# temperature.net
KiCad netlist of a schematic drawn in Altium Designer
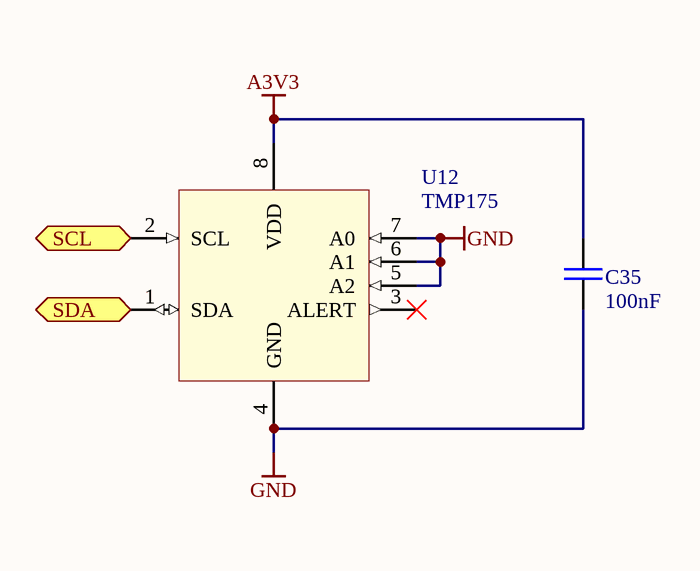
[diagram p0: temperature.SchDoc]

(export (version "E")
  (design (tool "Eeschema 10.0.6"))
  (components
    (comp (ref "C35")
      (value "100nF")
      (footprint "0603")
      (description "Capacitor")
      (fields (field (name "OWNER") "Nuno Brum"))
      (libsource (lib "Alcetronics_Devices") (part "CAP"))
    )
    (comp (ref "U12")
      (value "TMP175")
      (footprint "SOIC-8")
      (description "Digital Temperature Sensor")
      (libsource (lib "Alcetronics_IC") (part "TMP175"))
    )
  )
  (nets
    (net (code "1") (name "/SCL") (class "Default")
      (node (ref "U12") (pin "2") (pinfunction "SCL_2") (pintype "input"))
    )
    (net (code "2") (name "/SDA") (class "Default")
      (node (ref "U12") (pin "1") (pinfunction "SDA_1") (pintype "bidirectional"))
    )
    (net (code "3") (name "A3V3") (class "Default")
      (node (ref "C35") (pin "2") (pinfunction "2_2") (pintype "passive"))
      (node (ref "U12") (pin "8") (pinfunction "VDD_8") (pintype "power_in"))
    )
    (net (code "4") (name "GND") (class "Default")
      (node (ref "C35") (pin "1") (pinfunction "1_1") (pintype "passive"))
      (node (ref "U12") (pin "4") (pinfunction "GND_4") (pintype "power_in"))
      (node (ref "U12") (pin "5") (pinfunction "A2_5") (pintype "input"))
      (node (ref "U12") (pin "6") (pinfunction "A1_6") (pintype "input"))
      (node (ref "U12") (pin "7") (pinfunction "A0_7") (pintype "input"))
    )
    (net (code "5") (name "unconnected-(U12-ALERT-Pad3)") (class "Default")
      (node (ref "U12") (pin "3") (pinfunction "ALERT_3") (pintype "output+no_connect"))
    )
  )
)
